# Zio_9DOF_IMU_BNO055.net
KiCad netlist of a schematic drawn in EAGLE
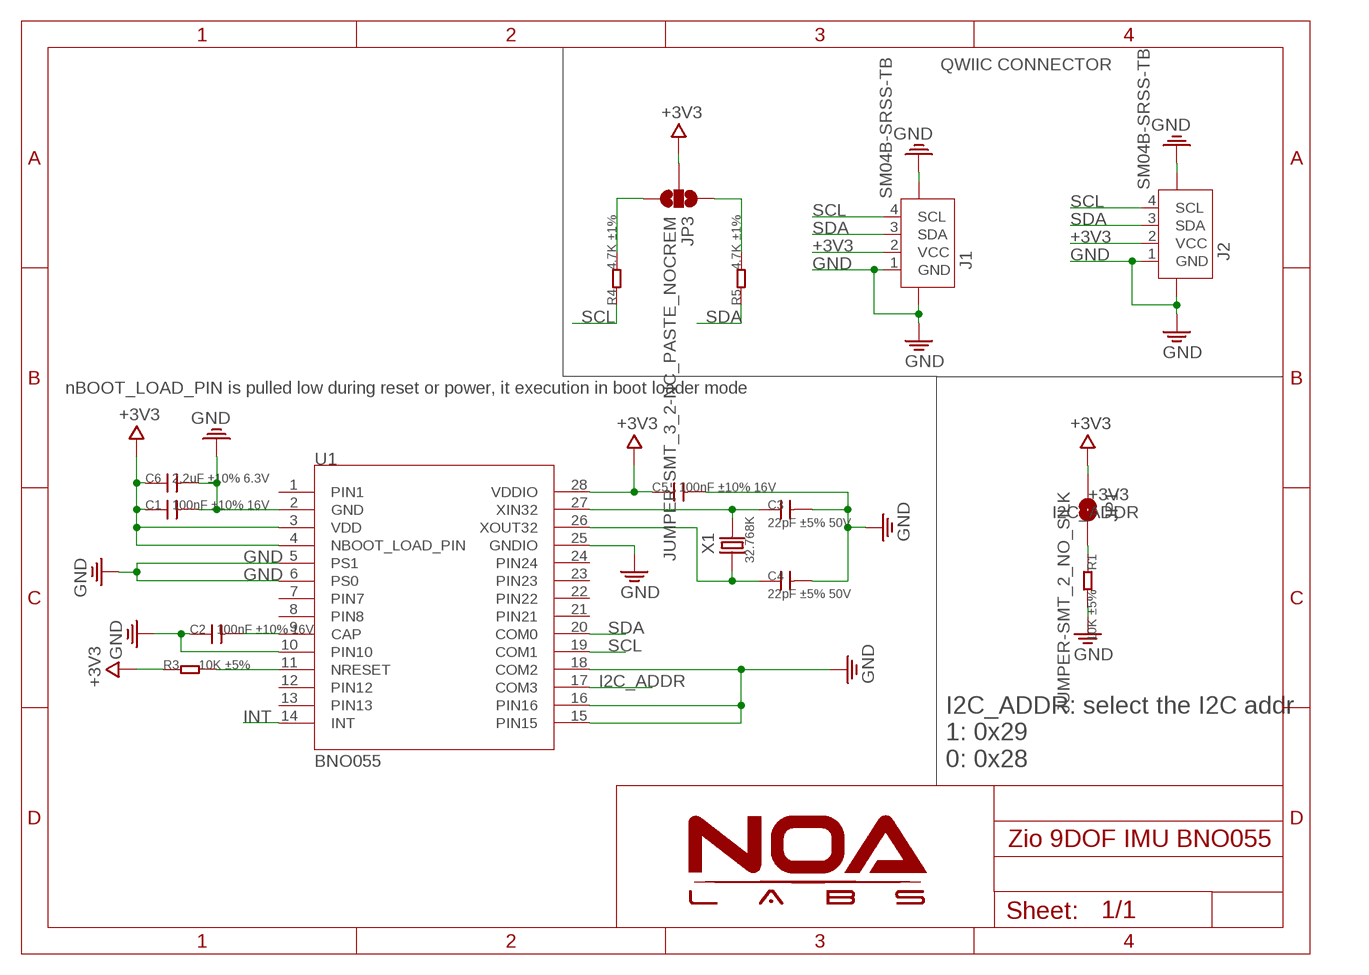
[diagram p0: schematic, sheet 1]

(export (version "E")
  (design (tool "Eeschema 10.0.6"))
  (components
    (comp (ref "C1")
      (value "100nF ±10% 16V")
      (footprint "eagle-import:0402")
      (libsource (lib "eagle-import") (part "C-0402"))
    )
    (comp (ref "C2")
      (value "100nF ±10% 16V")
      (footprint "eagle-import:0402")
      (libsource (lib "eagle-import") (part "C-0402"))
    )
    (comp (ref "C3")
      (value "22pF ±5% 50V")
      (footprint "eagle-import:0402")
      (libsource (lib "eagle-import") (part "C-0402"))
    )
    (comp (ref "C4")
      (value "22pF ±5% 50V")
      (footprint "eagle-import:0402")
      (libsource (lib "eagle-import") (part "C-0402"))
    )
    (comp (ref "C5")
      (value "100nF ±10% 16V")
      (footprint "eagle-import:0402")
      (libsource (lib "eagle-import") (part "C-0402"))
    )
    (comp (ref "C6")
      (value "2.2uF ±10% 6.3V")
      (footprint "eagle-import:0402")
      (libsource (lib "eagle-import") (part "C-0402"))
    )
    (comp (ref "J1")
      (value "SM04B-SRSS-TB")
      (footprint "eagle-import:JST-SH-4P")
      (libsource (lib "eagle-import") (part "JST-SH-4P-1.0"))
    )
    (comp (ref "J2")
      (value "SM04B-SRSS-TB")
      (footprint "eagle-import:JST-SH-4P")
      (libsource (lib "eagle-import") (part "JST-SH-4P-1.0"))
    )
    (comp (ref "JP1")
      (value "JUMPER-SMT_2_NO_SILK")
      (footprint "eagle-import:SMT-JUMPER_2_NO_SILK")
      (libsource (lib "eagle-import") (part "JUMPER-SMT_2_NO_SILK"))
    )
    (comp (ref "JP3")
      (value "JUMPER-SMT_3_2-NC_PASTE_NOCREM")
      (footprint "eagle-import:SMT-JUMPER_3_2-NC_PASTE_SILK_NOCREM")
      (libsource (lib "eagle-import") (part "JUMPER-SMT_3_2-NC_PASTE_NOCREM"))
    )
    (comp (ref "R1")
      (value "10K ±5%")
      (footprint "eagle-import:0402")
      (libsource (lib "eagle-import") (part "R-0402"))
    )
    (comp (ref "R3")
      (value "10K ±5%")
      (footprint "eagle-import:0402")
      (libsource (lib "eagle-import") (part "R-0402"))
    )
    (comp (ref "R4")
      (value "4.7K ±1%")
      (footprint "eagle-import:0402")
      (libsource (lib "eagle-import") (part "Discretex_R-0402"))
    )
    (comp (ref "R5")
      (value "4.7K ±1%")
      (footprint "eagle-import:0402")
      (libsource (lib "eagle-import") (part "Discretex_R-0402"))
    )
    (comp (ref "U1")
      (value "BNO055")
      (footprint "eagle-import:LGA-28_3.80X5.20_0.5")
      (libsource (lib "eagle-import") (part "BNO055"))
    )
    (comp (ref "X1")
      (value "32.768K")
      (footprint "eagle-import:2.0X12MM")
      (libsource (lib "eagle-import") (part "CRYSTAL-2012"))
    )
  )
  (nets
    (net (code "1") (name "+3V3") (class "Default")
      (node (ref "C1") (pin "1") (pinfunction "1_1") (pintype "passive"))
      (node (ref "C5") (pin "1") (pinfunction "1_1") (pintype "passive"))
      (node (ref "C6") (pin "1") (pinfunction "1_1") (pintype "passive"))
      (node (ref "J1") (pin "2") (pinfunction "VCC_2") (pintype "bidirectional"))
      (node (ref "J2") (pin "2") (pinfunction "VCC_2") (pintype "bidirectional"))
      (node (ref "JP1") (pin "1") (pinfunction "1_1") (pintype "passive"))
      (node (ref "JP3") (pin "2") (pinfunction "2_2") (pintype "passive"))
      (node (ref "R3") (pin "1") (pinfunction "1_1") (pintype "passive"))
      (node (ref "U1") (pin "28") (pinfunction "VDDIO_28") (pintype "bidirectional"))
      (node (ref "U1") (pin "3") (pinfunction "VDD_3") (pintype "bidirectional"))
      (node (ref "U1") (pin "4") (pinfunction "NBOOT_LOAD_PIN_4") (pintype "bidirectional"))
    )
    (net (code "2") (name "/I2C_ADDR") (class "Default")
      (node (ref "JP1") (pin "2") (pinfunction "2_2") (pintype "passive"))
      (node (ref "R1") (pin "1") (pinfunction "1_1") (pintype "passive"))
      (node (ref "U1") (pin "17") (pinfunction "COM3_17") (pintype "bidirectional"))
    )
    (net (code "3") (name "/INT") (class "Default")
      (node (ref "U1") (pin "14") (pinfunction "INT_14") (pintype "bidirectional"))
    )
    (net (code "4") (name "/SCL") (class "Default")
      (node (ref "J1") (pin "4") (pinfunction "SCL_4") (pintype "bidirectional"))
      (node (ref "J2") (pin "4") (pinfunction "SCL_4") (pintype "bidirectional"))
      (node (ref "R4") (pin "1") (pinfunction "1_1") (pintype "passive"))
      (node (ref "U1") (pin "19") (pinfunction "COM1_19") (pintype "bidirectional"))
    )
    (net (code "5") (name "/SDA") (class "Default")
      (node (ref "J1") (pin "3") (pinfunction "SDA_3") (pintype "bidirectional"))
      (node (ref "J2") (pin "3") (pinfunction "SDA_3") (pintype "bidirectional"))
      (node (ref "R5") (pin "1") (pinfunction "1_1") (pintype "passive"))
      (node (ref "U1") (pin "20") (pinfunction "COM0_20") (pintype "bidirectional"))
    )
    (net (code "6") (name "GND") (class "Default")
      (node (ref "C1") (pin "2") (pinfunction "2_2") (pintype "passive"))
      (node (ref "C2") (pin "1") (pinfunction "1_1") (pintype "passive"))
      (node (ref "C3") (pin "2") (pinfunction "2_2") (pintype "passive"))
      (node (ref "C4") (pin "2") (pinfunction "2_2") (pintype "passive"))
      (node (ref "C5") (pin "2") (pinfunction "2_2") (pintype "passive"))
      (node (ref "C6") (pin "2") (pinfunction "2_2") (pintype "passive"))
      (node (ref "J1") (pin "1") (pinfunction "GND_1") (pintype "bidirectional"))
      (node (ref "J1") (pin "NC1") (pinfunction "5_NC1") (pintype "bidirectional"))
      (node (ref "J1") (pin "NC2") (pinfunction "6_NC2") (pintype "bidirectional"))
      (node (ref "J2") (pin "1") (pinfunction "GND_1") (pintype "bidirectional"))
      (node (ref "J2") (pin "NC1") (pinfunction "5_NC1") (pintype "bidirectional"))
      (node (ref "J2") (pin "NC2") (pinfunction "6_NC2") (pintype "bidirectional"))
      (node (ref "R1") (pin "2") (pinfunction "2_2") (pintype "passive"))
      (node (ref "U1") (pin "10") (pinfunction "PIN10_10") (pintype "bidirectional"))
      (node (ref "U1") (pin "15") (pinfunction "PIN15_15") (pintype "bidirectional"))
      (node (ref "U1") (pin "16") (pinfunction "PIN16_16") (pintype "bidirectional"))
      (node (ref "U1") (pin "18") (pinfunction "COM2_18") (pintype "bidirectional"))
      (node (ref "U1") (pin "2") (pinfunction "GND_2") (pintype "bidirectional"))
      (node (ref "U1") (pin "25") (pinfunction "GNDIO_25") (pintype "bidirectional"))
      (node (ref "U1") (pin "5") (pinfunction "PS1_5") (pintype "bidirectional"))
      (node (ref "U1") (pin "6") (pinfunction "PS0_6") (pintype "bidirectional"))
    )
    (net (code "7") (name "Net-(JP3-Pad1)") (class "Default")
      (node (ref "JP3") (pin "1") (pinfunction "1_1") (pintype "passive"))
      (node (ref "R5") (pin "2") (pinfunction "2_2") (pintype "passive"))
    )
    (net (code "8") (name "Net-(JP3-Pad3)") (class "Default")
      (node (ref "JP3") (pin "3") (pinfunction "3_3") (pintype "passive"))
      (node (ref "R4") (pin "2") (pinfunction "2_2") (pintype "passive"))
    )
    (net (code "9") (name "Net-(U1-CAP)") (class "Default")
      (node (ref "C2") (pin "2") (pinfunction "2_2") (pintype "passive"))
      (node (ref "U1") (pin "9") (pinfunction "CAP_9") (pintype "bidirectional"))
    )
    (net (code "10") (name "Net-(U1-NRESET)") (class "Default")
      (node (ref "R3") (pin "2") (pinfunction "2_2") (pintype "passive"))
      (node (ref "U1") (pin "11") (pinfunction "NRESET_11") (pintype "bidirectional"))
    )
    (net (code "11") (name "Net-(U1-XIN32)") (class "Default")
      (node (ref "C3") (pin "1") (pinfunction "1_1") (pintype "passive"))
      (node (ref "U1") (pin "27") (pinfunction "XIN32_27") (pintype "bidirectional"))
      (node (ref "X1") (pin "2") (pinfunction "2_2") (pintype "passive"))
    )
    (net (code "12") (name "Net-(U1-XOUT32)") (class "Default")
      (node (ref "C4") (pin "1") (pinfunction "1_1") (pintype "passive"))
      (node (ref "U1") (pin "26") (pinfunction "XOUT32_26") (pintype "bidirectional"))
      (node (ref "X1") (pin "1") (pinfunction "1_1") (pintype "passive"))
    )
    (net (code "13") (name "unconnected-(U1-PIN1-Pad1)") (class "Default")
      (node (ref "U1") (pin "1") (pinfunction "PIN1_1") (pintype "bidirectional"))
    )
    (net (code "14") (name "unconnected-(U1-PIN7-Pad7)") (class "Default")
      (node (ref "U1") (pin "7") (pinfunction "PIN7_7") (pintype "bidirectional"))
    )
    (net (code "15") (name "unconnected-(U1-PIN8-Pad8)") (class "Default")
      (node (ref "U1") (pin "8") (pinfunction "PIN8_8") (pintype "bidirectional"))
    )
    (net (code "16") (name "unconnected-(U1-PIN12-Pad12)") (class "Default")
      (node (ref "U1") (pin "12") (pinfunction "PIN12_12") (pintype "bidirectional"))
    )
    (net (code "17") (name "unconnected-(U1-PIN13-Pad13)") (class "Default")
      (node (ref "U1") (pin "13") (pinfunction "PIN13_13") (pintype "bidirectional"))
    )
    (net (code "18") (name "unconnected-(U1-PIN21-Pad21)") (class "Default")
      (node (ref "U1") (pin "21") (pinfunction "PIN21_21") (pintype "bidirectional"))
    )
    (net (code "19") (name "unconnected-(U1-PIN22-Pad22)") (class "Default")
      (node (ref "U1") (pin "22") (pinfunction "PIN22_22") (pintype "bidirectional"))
    )
    (net (code "20") (name "unconnected-(U1-PIN23-Pad23)") (class "Default")
      (node (ref "U1") (pin "23") (pinfunction "PIN23_23") (pintype "bidirectional"))
    )
    (net (code "21") (name "unconnected-(U1-PIN24-Pad24)") (class "Default")
      (node (ref "U1") (pin "24") (pinfunction "PIN24_24") (pintype "bidirectional"))
    )
  )
)
